# AI-EYE.net
KiCad netlist of a schematic drawn in Altium Designer
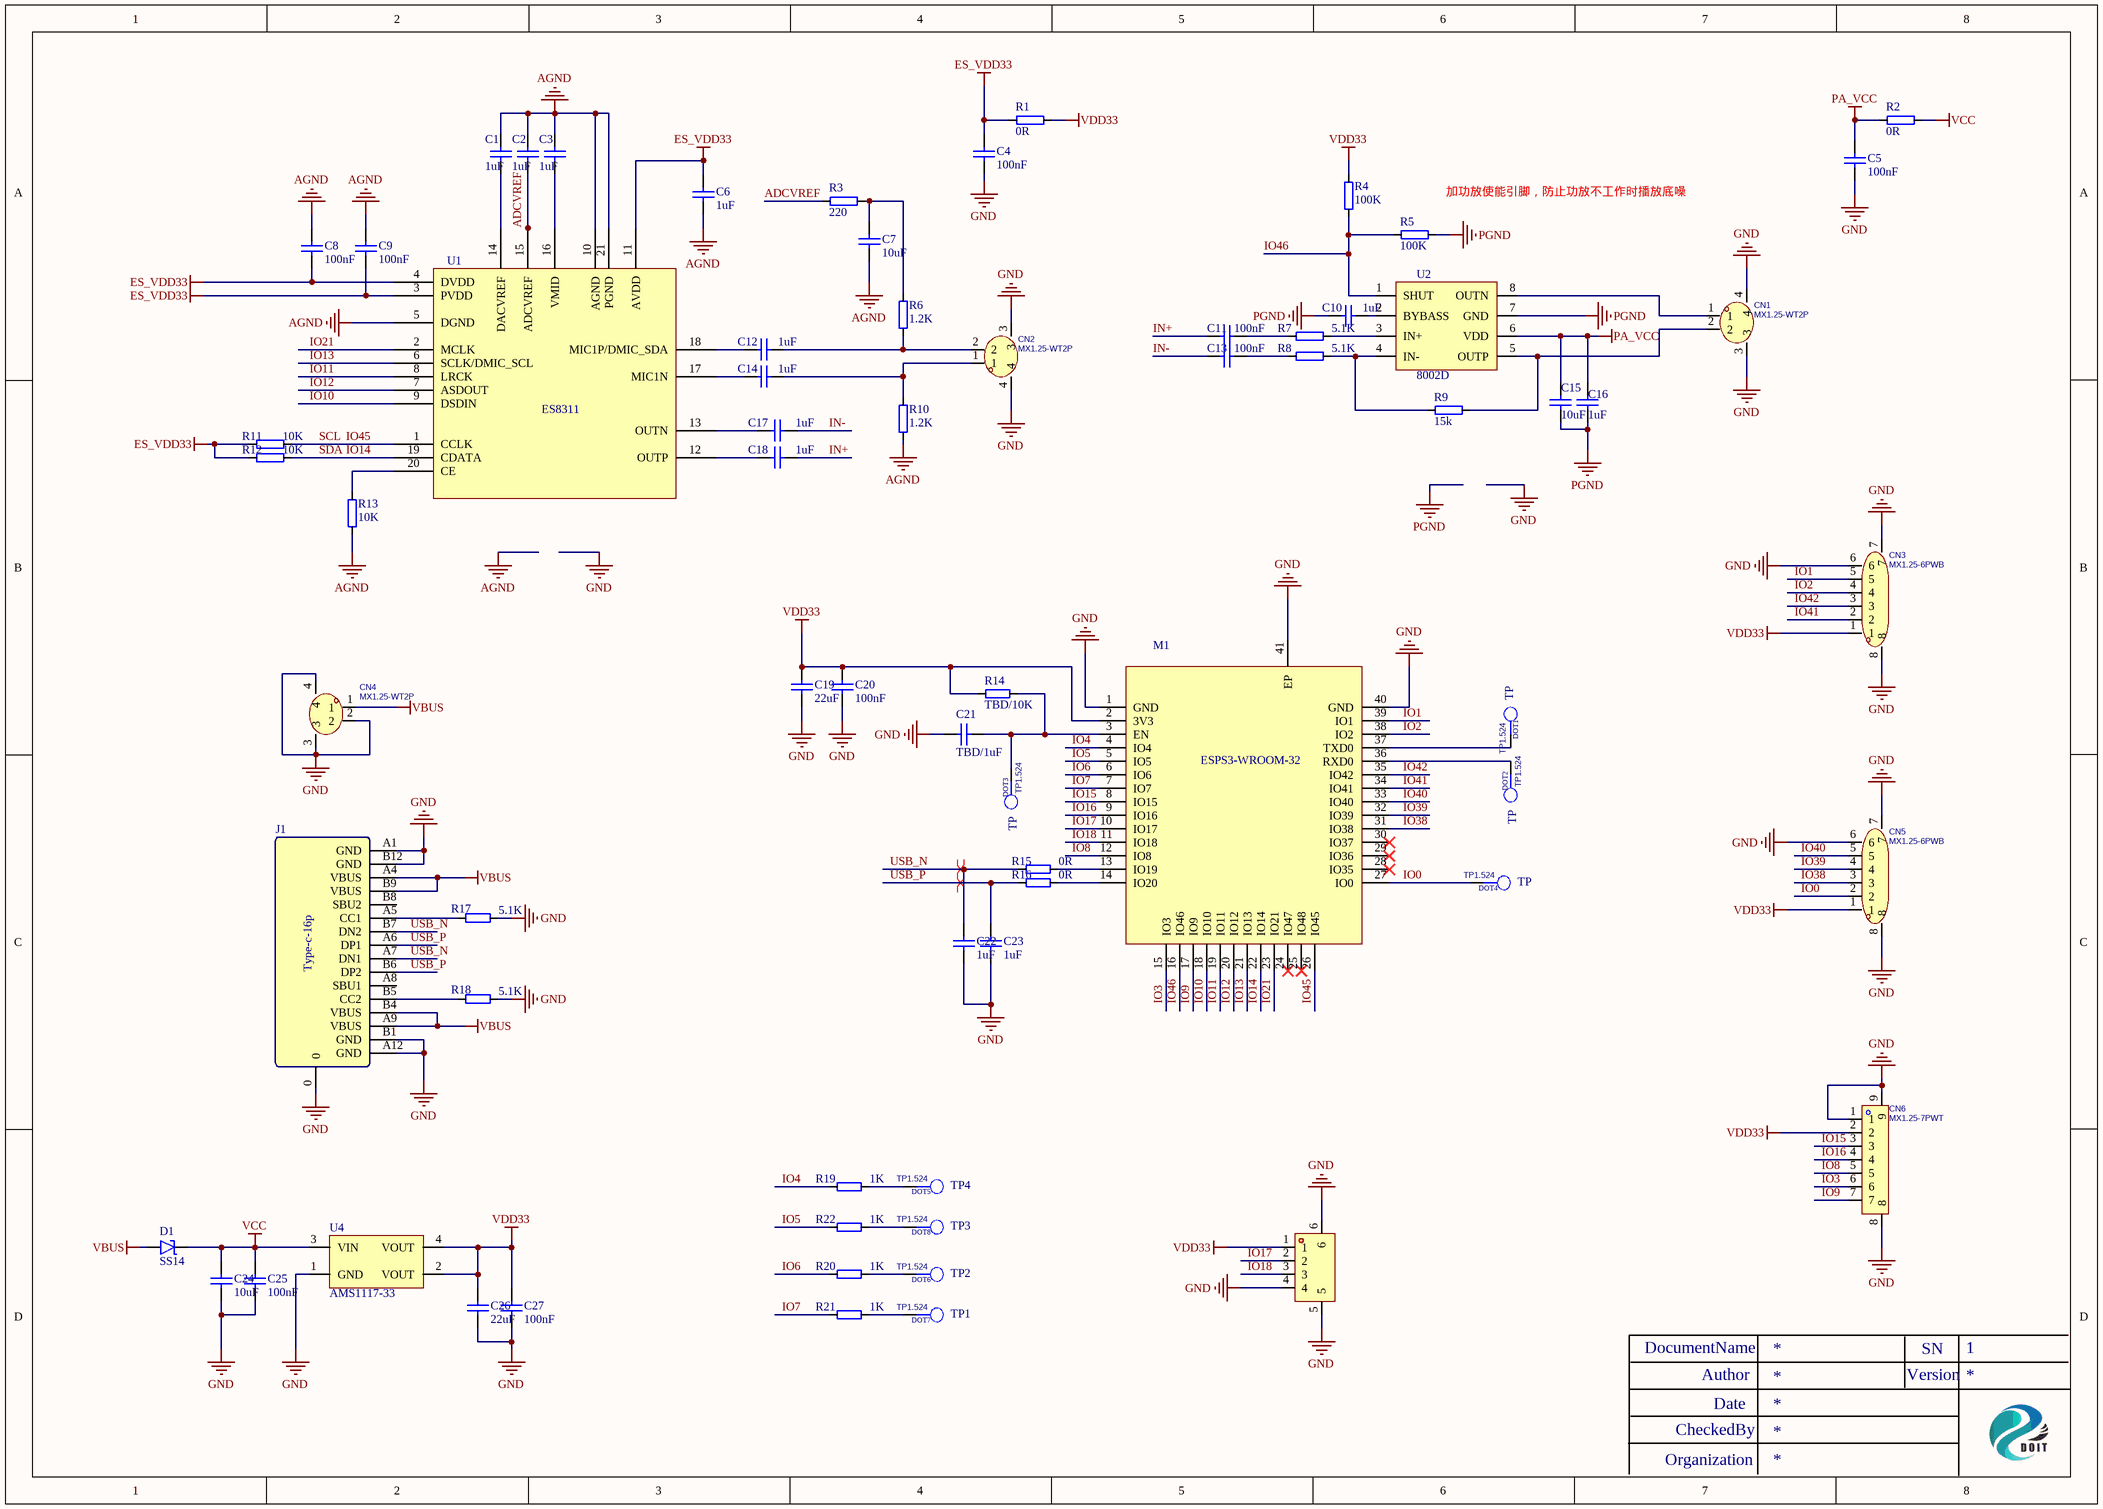
[diagram p0: AI-EYE.SchDoc]

(export (version "E")
  (design (tool "Eeschema 10.0.6"))
  (components
    (comp (ref "C1") (value "1uF") (footprint "0402C") (libsource (lib "accessory") (part "CAP-SMD")))
    (comp (ref "C2") (value "1uF") (footprint "0402C") (libsource (lib "accessory") (part "CAP-SMD")))
    (comp (ref "C3") (value "1uF") (footprint "0402C") (libsource (lib "accessory") (part "CAP-SMD")))
    (comp (ref "C4") (value "100nF") (footprint "0402C") (libsource (lib "accessory") (part "CAP-SMD")))
    (comp (ref "C5") (value "100nF") (footprint "0402C") (libsource (lib "accessory") (part "CAP-SMD")))
    (comp (ref "C6") (value "1uF") (footprint "0402C") (libsource (lib "accessory") (part "CAP-SMD")))
    (comp (ref "C7") (value "10uF") (footprint "0402C") (libsource (lib "accessory") (part "CAP-SMD")))
    (comp (ref "C8") (value "100nF") (footprint "0402C") (libsource (lib "accessory") (part "CAP-SMD")))
    (comp (ref "C9") (value "100nF") (footprint "0402C") (libsource (lib "accessory") (part "CAP-SMD")))
    (comp (ref "C10") (value "1uF") (footprint "0402C") (libsource (lib "accessory") (part "CAP-SMD")))
    (comp (ref "C11") (value "100nF") (footprint "0402C") (libsource (lib "accessory") (part "CAP-SMD")))
    (comp (ref "C12") (value "1uF") (footprint "0402C") (libsource (lib "accessory") (part "CAP-SMD")))
    (comp (ref "C13") (value "100nF") (footprint "0402C") (libsource (lib "accessory") (part "CAP-SMD")))
    (comp (ref "C14") (value "1uF") (footprint "0402C") (libsource (lib "accessory") (part "CAP-SMD")))
    (comp (ref "C15") (value "10uF") (footprint "0402C") (libsource (lib "accessory") (part "CAP-SMD")))
    (comp (ref "C16") (value "1uF") (footprint "0402C") (libsource (lib "accessory") (part "CAP-SMD")))
    (comp (ref "C17") (value "1uF") (footprint "0402C") (libsource (lib "accessory") (part "CAP-SMD")))
    (comp (ref "C18") (value "1uF") (footprint "0402C") (libsource (lib "accessory") (part "CAP-SMD")))
    (comp (ref "C19") (value "22uF") (footprint "0603C") (libsource (lib "accessory") (part "CAP-SMD")))
    (comp (ref "C20") (value "100nF") (footprint "0603C") (libsource (lib "accessory") (part "CAP-SMD")))
    (comp (ref "C21") (value "TBD/1uF") (footprint "0402C") (libsource (lib "accessory") (part "CAP-SMD")))
    (comp (ref "C22") (value "1uF") (footprint "0402C") (libsource (lib "accessory") (part "CAP-SMD")))
    (comp (ref "C23") (value "1uF") (footprint "0402C") (libsource (lib "accessory") (part "CAP-SMD")))
    (comp (ref "C24") (value "10uF") (footprint "0603C") (libsource (lib "accessory") (part "CAP-SMD")))
    (comp (ref "C25") (value "100nF") (footprint "0603C") (libsource (lib "accessory") (part "CAP-SMD")))
    (comp (ref "C26") (value "22uF") (footprint "0603C") (libsource (lib "accessory") (part "CAP-SMD")))
    (comp (ref "C27") (value "100nF") (footprint "0603C") (libsource (lib "accessory") (part "CAP-SMD")))
    (comp (ref "CN1")
      (value "MX1.25-WT2P")
      (footprint "CONN-SMD_2P-P1.25-WT2P")
      (fields (field (name "MANUFACTURER") "Megastar(兆星)"))
      (libsource (lib "connector") (part "CONN-MX1.25-2P"))
    )
    (comp (ref "CN2")
      (value "MX1.25-WT2P")
      (footprint "CONN-SMD_2P-P1.25-WT2P")
      (fields (field (name "MANUFACTURER") "Megastar(兆星)"))
      (libsource (lib "connector") (part "CONN-MX1.25-2P"))
    )
    (comp (ref "CN3")
      (value "MX1.25-6PWB")
      (footprint "CONN-SMD_6P-P1.25_XUNPU_WAFER-MX1.25-6PWB")
      (fields
        (field (name "MANUFACTURER") "XUNPU(讯普)")
        (field (name "MANUFACTURER PART") "WAFER-MX1.25-6PWB")
      )
      (libsource (lib "connector") (part "CONN-MX1.25-6PWB"))
    )
    (comp (ref "CN4")
      (value "MX1.25-WT2P")
      (footprint "CONN-SMD_2P-P1.25-WT2P")
      (fields (field (name "MANUFACTURER") "Megastar(兆星)"))
      (libsource (lib "connector") (part "CONN-MX1.25-2P"))
    )
    (comp (ref "CN5")
      (value "MX1.25-6PWB")
      (footprint "CONN-SMD_6P-P1.25_XUNPU_WAFER-MX1.25-6PWB")
      (fields
        (field (name "MANUFACTURER") "XUNPU(讯普)")
        (field (name "MANUFACTURER PART") "WAFER-MX1.25-6PWB")
      )
      (libsource (lib "connector") (part "CONN-MX1.25-6PWB"))
    )
    (comp (ref "CN6")
      (value "MX1.25-7PWT")
      (footprint "CONN-SMD_7P-P1.25_MX1.25-7PWT")
      (fields (field (name "MANUFACTURER") "Bossie(博锡)") (field (name "MANUFACTURER PART") "BX-MX1.25-7PWT"))
      (libsource (lib "connector") (part "CONN-MX1.25-7PWT"))
    )
    (comp (ref "D1")
      (value "SS14")
      (footprint "SOD123")
      (description "Schottky diode")
      (libsource (lib "accessory") (part "D"))
    )
    (comp (ref "DOT1")
      (value "TP")
      (footprint "TP-1.524")
      (fields (field (name "PCB FOOTPRINT") "TP1.524"))
      (libsource (lib "accessory") (part "TP"))
    )
    (comp (ref "DOT2")
      (value "TP")
      (footprint "TP-1.524")
      (fields (field (name "PCB FOOTPRINT") "TP1.524"))
      (libsource (lib "accessory") (part "TP"))
    )
    (comp (ref "DOT3")
      (value "TP")
      (footprint "TP-1.524")
      (fields (field (name "PCB FOOTPRINT") "TP1.524"))
      (libsource (lib "accessory") (part "TP"))
    )
    (comp (ref "DOT4")
      (value "TP")
      (footprint "TP-1.524")
      (fields (field (name "PCB FOOTPRINT") "TP1.524"))
      (libsource (lib "accessory") (part "TP"))
    )
    (comp (ref "DOT5")
      (value "TP4")
      (footprint "TP-5")
      (fields (field (name "PCB FOOTPRINT") "TP1.524"))
      (libsource (lib "accessory") (part "TP"))
    )
    (comp (ref "DOT6")
      (value "TP2")
      (footprint "TP-5")
      (fields (field (name "PCB FOOTPRINT") "TP1.524"))
      (libsource (lib "accessory") (part "TP"))
    )
    (comp (ref "DOT7")
      (value "TP1")
      (footprint "TP-5")
      (fields (field (name "PCB FOOTPRINT") "TP1.524"))
      (libsource (lib "accessory") (part "TP"))
    )
    (comp (ref "DOT8")
      (value "TP3")
      (footprint "TP-5")
      (fields (field (name "PCB FOOTPRINT") "TP1.524"))
      (libsource (lib "accessory") (part "TP"))
    )
    (comp (ref "J1")
      (value "Type-c-16p")
      (footprint "USB-TYPE-C")
      (libsource (lib "connector") (part "USB-TYPE-C"))
    )
    (comp (ref "M1")
      (value "ESPS3-WROOM-32")
      (footprint "ESPS3-WROOM-32")
      (libsource (lib "DOIT-MZ") (part "ESPS3-WROOM-32"))
    )
    (comp (ref "R1")
      (value "0R")
      (footprint "0402R")
      (description "Resistor")
      (libsource (lib "") (part "Res_1"))
    )
    (comp (ref "R2")
      (value "0R")
      (footprint "0402R")
      (description "Resistor")
      (libsource (lib "") (part "Res_1"))
    )
    (comp (ref "R3")
      (value "220")
      (footprint "0402R")
      (description "Resistor")
      (libsource (lib "") (part "Res_1"))
    )
    (comp (ref "R4")
      (value "100K")
      (footprint "0402R")
      (description "Resistor")
      (libsource (lib "") (part "Res_1"))
    )
    (comp (ref "R5")
      (value "100K")
      (footprint "0402R")
      (description "Resistor")
      (libsource (lib "") (part "Res_1"))
    )
    (comp (ref "R6")
      (value "1.2K")
      (footprint "0402R")
      (description "Resistor")
      (libsource (lib "") (part "Res_1"))
    )
    (comp (ref "R7")
      (value "5.1K")
      (footprint "0402R")
      (description "Resistor")
      (libsource (lib "") (part "Res_1"))
    )
    (comp (ref "R8")
      (value "5.1K")
      (footprint "0402R")
      (description "Resistor")
      (libsource (lib "") (part "Res_1"))
    )
    (comp (ref "R9")
      (value "15k")
      (footprint "0402R")
      (description "Resistor")
      (libsource (lib "") (part "Res_1"))
    )
    (comp (ref "R10")
      (value "1.2K")
      (footprint "0402R")
      (description "Resistor")
      (libsource (lib "") (part "Res_1"))
    )
    (comp (ref "R11")
      (value "10K")
      (footprint "0402R")
      (description "Resistor")
      (libsource (lib "") (part "Res_1"))
    )
    (comp (ref "R12")
      (value "10K")
      (footprint "0402R")
      (description "Resistor")
      (libsource (lib "") (part "Res_1"))
    )
    (comp (ref "R13")
      (value "10K")
      (footprint "0402R")
      (description "Resistor")
      (libsource (lib "") (part "Res_1"))
    )
    (comp (ref "R14")
      (value "TBD/10K")
      (footprint "0603R")
      (description "Resistor")
      (libsource (lib "accessory") (part "Res"))
    )
    (comp (ref "R15")
      (value "0R")
      (footprint "0402R")
      (description "Resistor")
      (libsource (lib "accessory") (part "Res"))
    )
    (comp (ref "R16")
      (value "0R")
      (footprint "0402R")
      (description "Resistor")
      (libsource (lib "accessory") (part "Res"))
    )
    (comp (ref "R17")
      (value "5.1K")
      (footprint "0402R")
      (description "Resistor")
      (libsource (lib "accessory") (part "Res"))
    )
    (comp (ref "R18")
      (value "5.1K")
      (footprint "0402R")
      (description "Resistor")
      (libsource (lib "accessory") (part "Res"))
    )
    (comp (ref "R19")
      (value "1K")
      (footprint "0402R")
      (description "Resistor")
      (libsource (lib "accessory") (part "Res"))
    )
    (comp (ref "R20")
      (value "1K")
      (footprint "0402R")
      (description "Resistor")
      (libsource (lib "accessory") (part "Res"))
    )
    (comp (ref "R21")
      (value "1K")
      (footprint "0402R")
      (description "Resistor")
      (libsource (lib "accessory") (part "Res"))
    )
    (comp (ref "R22")
      (value "1K")
      (footprint "0402R")
      (description "Resistor")
      (libsource (lib "accessory") (part "Res"))
    )
    (comp (ref "U1") (value "ES8311") (footprint "QFN-20-3X3") (libsource (lib "chip") (part "ES8311")))
    (comp (ref "U2") (value "8002D") (footprint "SOP8-1.27*5.4") (libsource (lib "chip") (part "8002D")))
    (comp (ref "U4") (value "AMS1117-33") (footprint "SOT-223") (libsource (lib "chip") (part "AMS1117-33")))
    (comp (ref "U5")
      (value "ZX-MX1.25-4PWT")
      (footprint "CONN-SMD_4P-P1.25-MX1.25-4P-WT")
      (fields (field (name "MANUFACTURER") "Megastar(兆星)"))
      (libsource (lib "connector") (part "CONN-MX1.25-4PWT"))
    )
  )
  (nets
    (net (code "1") (name "/ADCVREF") (class "Default")
      (node (ref "C2") (pin "1") (pinfunction "1_1") (pintype "passive"))
      (node (ref "R3") (pin "2") (pintype "passive"))
      (node (ref "U1") (pin "15") (pinfunction "ADCVREF_15") (pintype "passive"))
    )
    (net (code "2") (name "/IN+") (class "Default")
      (node (ref "C11") (pin "2") (pinfunction "2_2") (pintype "passive"))
      (node (ref "C18") (pin "1") (pinfunction "1_1") (pintype "passive"))
    )
    (net (code "3") (name "/IN-") (class "Default")
      (node (ref "C13") (pin "2") (pinfunction "2_2") (pintype "passive"))
      (node (ref "C17") (pin "1") (pinfunction "1_1") (pintype "passive"))
    )
    (net (code "4") (name "/IO0") (class "Default")
      (node (ref "CN5") (pin "2") (pinfunction "2_2") (pintype "passive"))
      (node (ref "DOT4") (pin "1") (pinfunction "1_1") (pintype "passive"))
      (node (ref "M1") (pin "27") (pinfunction "IO0_27") (pintype "passive"))
    )
    (net (code "5") (name "/IO1") (class "Default")
      (node (ref "CN3") (pin "5") (pinfunction "5_5") (pintype "passive"))
      (node (ref "M1") (pin "39") (pinfunction "IO1_39") (pintype "passive"))
    )
    (net (code "6") (name "/IO2") (class "Default")
      (node (ref "CN3") (pin "4") (pinfunction "4_4") (pintype "passive"))
      (node (ref "M1") (pin "38") (pinfunction "IO2_38") (pintype "passive"))
    )
    (net (code "7") (name "/IO3") (class "Default")
      (node (ref "CN6") (pin "6") (pinfunction "6_6") (pintype "passive"))
      (node (ref "M1") (pin "15") (pinfunction "IO3_15") (pintype "passive"))
    )
    (net (code "8") (name "/IO4") (class "Default")
      (node (ref "M1") (pin "4") (pinfunction "IO4_4") (pintype "passive"))
      (node (ref "R19") (pin "2") (pintype "passive"))
    )
    (net (code "9") (name "/IO5") (class "Default")
      (node (ref "M1") (pin "5") (pinfunction "IO5_5") (pintype "passive"))
      (node (ref "R22") (pin "2") (pintype "passive"))
    )
    (net (code "10") (name "/IO6") (class "Default")
      (node (ref "M1") (pin "6") (pinfunction "IO6_6") (pintype "passive"))
      (node (ref "R20") (pin "2") (pintype "passive"))
    )
    (net (code "11") (name "/IO7") (class "Default")
      (node (ref "M1") (pin "7") (pinfunction "IO7_7") (pintype "passive"))
      (node (ref "R21") (pin "2") (pintype "passive"))
    )
    (net (code "12") (name "/IO8") (class "Default")
      (node (ref "CN6") (pin "5") (pinfunction "5_5") (pintype "passive"))
      (node (ref "M1") (pin "12") (pinfunction "IO8_12") (pintype "passive"))
    )
    (net (code "13") (name "/IO9") (class "Default")
      (node (ref "CN6") (pin "7") (pinfunction "7_7") (pintype "passive"))
      (node (ref "M1") (pin "17") (pinfunction "IO9_17") (pintype "passive"))
    )
    (net (code "14") (name "/IO10") (class "Default")
      (node (ref "M1") (pin "18") (pinfunction "IO10_18") (pintype "passive"))
      (node (ref "U1") (pin "9") (pinfunction "DSDIN_9") (pintype "passive"))
    )
    (net (code "15") (name "/IO11") (class "Default")
      (node (ref "M1") (pin "19") (pinfunction "IO11_19") (pintype "passive"))
      (node (ref "U1") (pin "8") (pinfunction "LRCK_8") (pintype "passive"))
    )
    (net (code "16") (name "/IO12") (class "Default")
      (node (ref "M1") (pin "20") (pinfunction "IO12_20") (pintype "passive"))
      (node (ref "U1") (pin "7") (pinfunction "ASDOUT_7") (pintype "passive"))
    )
    (net (code "17") (name "/IO13") (class "Default")
      (node (ref "M1") (pin "21") (pinfunction "IO13_21") (pintype "passive"))
      (node (ref "U1") (pin "6") (pinfunction "SCLK/DMIC_SCL_6") (pintype "passive"))
    )
    (net (code "18") (name "/IO14") (class "Default")
      (node (ref "M1") (pin "22") (pinfunction "IO14_22") (pintype "passive"))
      (node (ref "R12") (pin "2") (pintype "passive"))
      (node (ref "U1") (pin "19") (pinfunction "CDATA_19") (pintype "passive"))
    )
    (net (code "19") (name "/IO15") (class "Default")
      (node (ref "CN6") (pin "3") (pinfunction "3_3") (pintype "passive"))
      (node (ref "M1") (pin "8") (pinfunction "IO15_8") (pintype "passive"))
    )
    (net (code "20") (name "/IO16") (class "Default")
      (node (ref "CN6") (pin "4") (pinfunction "4_4") (pintype "passive"))
      (node (ref "M1") (pin "9") (pinfunction "IO16_9") (pintype "passive"))
    )
    (net (code "21") (name "/IO17") (class "Default")
      (node (ref "M1") (pin "10") (pinfunction "IO17_10") (pintype "passive"))
      (node (ref "U5") (pin "2") (pinfunction "2_2") (pintype "passive"))
    )
    (net (code "22") (name "/IO18") (class "Default")
      (node (ref "M1") (pin "11") (pinfunction "IO18_11") (pintype "passive"))
      (node (ref "U5") (pin "3") (pinfunction "3_3") (pintype "passive"))
    )
    (net (code "23") (name "/IO21") (class "Default")
      (node (ref "M1") (pin "23") (pinfunction "IO21_23") (pintype "passive"))
      (node (ref "U1") (pin "2") (pinfunction "MCLK_2") (pintype "passive"))
    )
    (net (code "24") (name "/IO38") (class "Default")
      (node (ref "CN5") (pin "3") (pinfunction "3_3") (pintype "passive"))
      (node (ref "M1") (pin "31") (pinfunction "IO38_31") (pintype "passive"))
    )
    (net (code "25") (name "/IO39") (class "Default")
      (node (ref "CN5") (pin "4") (pinfunction "4_4") (pintype "passive"))
      (node (ref "M1") (pin "32") (pinfunction "IO39_32") (pintype "passive"))
    )
    (net (code "26") (name "/IO40") (class "Default")
      (node (ref "CN5") (pin "5") (pinfunction "5_5") (pintype "passive"))
      (node (ref "M1") (pin "33") (pinfunction "IO40_33") (pintype "passive"))
    )
    (net (code "27") (name "/IO41") (class "Default")
      (node (ref "CN3") (pin "2") (pinfunction "2_2") (pintype "passive"))
      (node (ref "M1") (pin "34") (pinfunction "IO41_34") (pintype "passive"))
    )
    (net (code "28") (name "/IO42") (class "Default")
      (node (ref "CN3") (pin "3") (pinfunction "3_3") (pintype "passive"))
      (node (ref "M1") (pin "35") (pinfunction "IO42_35") (pintype "passive"))
    )
    (net (code "29") (name "/IO45") (class "Default")
      (node (ref "M1") (pin "26") (pinfunction "IO45_26") (pintype "passive"))
      (node (ref "R11") (pin "2") (pintype "passive"))
      (node (ref "U1") (pin "1") (pinfunction "CCLK_1") (pintype "passive"))
    )
    (net (code "30") (name "/IO46") (class "Default")
      (node (ref "M1") (pin "16") (pinfunction "IO46_16") (pintype "passive"))
      (node (ref "R4") (pin "2") (pintype "passive"))
      (node (ref "R5") (pin "1") (pintype "passive"))
      (node (ref "U2") (pin "1") (pinfunction "SHUT_1") (pintype "passive"))
    )
    (net (code "31") (name "/USB_N") (class "Default")
      (node (ref "C22") (pin "1") (pinfunction "1_1") (pintype "passive"))
      (node (ref "J1") (pin "A7") (pinfunction "DN1_A7") (pintype "passive"))
      (node (ref "J1") (pin "B7") (pinfunction "DN2_B7") (pintype "passive"))
      (node (ref "R15") (pin "2") (pintype "passive"))
    )
    (net (code "32") (name "/USB_P") (class "Default")
      (node (ref "C23") (pin "1") (pinfunction "1_1") (pintype "passive"))
      (node (ref "J1") (pin "A6") (pinfunction "DP1_A6") (pintype "passive"))
      (node (ref "J1") (pin "B6") (pinfunction "DP2_B6") (pintype "passive"))
      (node (ref "R16") (pin "2") (pintype "passive"))
    )
    (net (code "33") (name "AGND") (class "Default")
      (node (ref "C1") (pin "2") (pinfunction "2_2") (pintype "passive"))
      (node (ref "C2") (pin "2") (pinfunction "2_2") (pintype "passive"))
      (node (ref "C3") (pin "2") (pinfunction "2_2") (pintype "passive"))
      (node (ref "C6") (pin "1") (pinfunction "1_1") (pintype "passive"))
      (node (ref "C7") (pin "2") (pinfunction "2_2") (pintype "passive"))
      (node (ref "C8") (pin "2") (pinfunction "2_2") (pintype "passive"))
      (node (ref "C9") (pin "2") (pinfunction "2_2") (pintype "passive"))
      (node (ref "R10") (pin "2") (pintype "passive"))
      (node (ref "R13") (pin "2") (pintype "passive"))
      (node (ref "U1") (pin "10") (pinfunction "AGND_10") (pintype "passive"))
      (node (ref "U1") (pin "21") (pinfunction "PGND_21") (pintype "passive"))
      (node (ref "U1") (pin "5") (pinfunction "DGND_5") (pintype "passive"))
    )
    (net (code "34") (name "ES_VDD33") (class "Default")
      (node (ref "C4") (pin "2") (pinfunction "2_2") (pintype "passive"))
      (node (ref "C6") (pin "2") (pinfunction "2_2") (pintype "passive"))
      (node (ref "C8") (pin "1") (pinfunction "1_1") (pintype "passive"))
      (node (ref "C9") (pin "1") (pinfunction "1_1") (pintype "passive"))
      (node (ref "R1") (pin "2") (pintype "passive"))
      (node (ref "R11") (pin "1") (pintype "passive"))
      (node (ref "R12") (pin "1") (pintype "passive"))
      (node (ref "U1") (pin "11") (pinfunction "AVDD_11") (pintype "passive"))
      (node (ref "U1") (pin "3") (pinfunction "PVDD_3") (pintype "passive"))
      (node (ref "U1") (pin "4") (pinfunction "DVDD_4") (pintype "passive"))
    )
    (net (code "35") (name "GND") (class "Default")
      (node (ref "C19") (pin "2") (pinfunction "2_2") (pintype "passive"))
      (node (ref "C20") (pin "2") (pinfunction "2_2") (pintype "passive"))
      (node (ref "C21") (pin "1") (pinfunction "1_1") (pintype "passive"))
      (node (ref "C22") (pin "2") (pinfunction "2_2") (pintype "passive"))
      (node (ref "C23") (pin "2") (pinfunction "2_2") (pintype "passive"))
      (node (ref "C24") (pin "2") (pinfunction "2_2") (pintype "passive"))
      (node (ref "C25") (pin "2") (pinfunction "2_2") (pintype "passive"))
      (node (ref "C26") (pin "2") (pinfunction "2_2") (pintype "passive"))
      (node (ref "C27") (pin "2") (pinfunction "2_2") (pintype "passive"))
      (node (ref "C4") (pin "1") (pinfunction "1_1") (pintype "passive"))
      (node (ref "C5") (pin "1") (pinfunction "1_1") (pintype "passive"))
      (node (ref "CN1") (pin "3") (pinfunction "3_3") (pintype "passive"))
      (node (ref "CN1") (pin "4") (pinfunction "4_4") (pintype "passive"))
      (node (ref "CN2") (pin "3") (pinfunction "3_3") (pintype "passive"))
      (node (ref "CN2") (pin "4") (pinfunction "4_4") (pintype "passive"))
      (node (ref "CN3") (pin "6") (pinfunction "6_6") (pintype "passive"))
      (node (ref "CN3") (pin "7") (pinfunction "7_7") (pintype "passive"))
      (node (ref "CN3") (pin "8") (pinfunction "8_8") (pintype "passive"))
      (node (ref "CN4") (pin "2") (pinfunction "2_2") (pintype "passive"))
      (node (ref "CN4") (pin "3") (pinfunction "3_3") (pintype "passive"))
      (node (ref "CN4") (pin "4") (pinfunction "4_4") (pintype "passive"))
      (node (ref "CN5") (pin "6") (pinfunction "6_6") (pintype "passive"))
      (node (ref "CN5") (pin "7") (pinfunction "7_7") (pintype "passive"))
      (node (ref "CN5") (pin "8") (pinfunction "8_8") (pintype "passive"))
      (node (ref "CN6") (pin "1") (pinfunction "1_1") (pintype "passive"))
      (node (ref "CN6") (pin "8") (pinfunction "8_8") (pintype "passive"))
      (node (ref "CN6") (pin "9") (pinfunction "9_9") (pintype "passive"))
      (node (ref "J1") (pin "0") (pinfunction "0_0") (pintype "passive"))
      (node (ref "J1") (pin "A1") (pinfunction "GND_A1") (pintype "passive"))
      (node (ref "J1") (pin "A12") (pinfunction "GND_A12") (pintype "passive"))
      (node (ref "J1") (pin "B1") (pinfunction "GND_B1") (pintype "passive"))
      (node (ref "J1") (pin "B12") (pinfunction "GND_B12") (pintype "passive"))
      (node (ref "M1") (pin "1") (pinfunction "GND_1") (pintype "passive"))
      (node (ref "M1") (pin "40") (pinfunction "GND_40") (pintype "passive"))
      (node (ref "M1") (pin "41") (pinfunction "EP_41") (pintype "passive"))
      (node (ref "R17") (pin "1") (pintype "passive"))
      (node (ref "R18") (pin "1") (pintype "passive"))
      (node (ref "U4") (pin "1") (pinfunction "GND_1") (pintype "passive"))
      (node (ref "U5") (pin "4") (pinfunction "4_4") (pintype "passive"))
      (node (ref "U5") (pin "5") (pinfunction "5_5") (pintype "passive"))
      (node (ref "U5") (pin "6") (pinfunction "6_6") (pintype "passive"))
    )
    (net (code "36") (name "Net-(C7-Pad1)") (class "Default")
      (node (ref "C7") (pin "1") (pinfunction "1_1") (pintype "passive"))
      (node (ref "R3") (pin "1") (pintype "passive"))
      (node (ref "R6") (pin "2") (pintype "passive"))
    )
    (net (code "37") (name "Net-(C11-Pad1)") (class "Default")
      (node (ref "C11") (pin "1") (pinfunction "1_1") (pintype "passive"))
      (node (ref "R7") (pin "2") (pintype "passive"))
    )
    (net (code "38") (name "Net-(C12-Pad1)") (class "Default")
      (node (ref "C12") (pin "1") (pinfunction "1_1") (pintype "passive"))
      (node (ref "CN2") (pin "2") (pinfunction "2_2") (pintype "passive"))
      (node (ref "R6") (pin "1") (pintype "passive"))
    )
    (net (code "39") (name "Net-(C13-Pad1)") (class "Default")
      (node (ref "C13") (pin "1") (pinfunction "1_1") (pintype "passive"))
      (node (ref "R8") (pin "2") (pintype "passive"))
    )
    (net (code "40") (name "Net-(C14-Pad1)") (class "Default")
      (node (ref "C14") (pin "1") (pinfunction "1_1") (pintype "passive"))
      (node (ref "CN2") (pin "1") (pinfunction "1_1") (pintype "passive"))
      (node (ref "R10") (pin "1") (pintype "passive"))
    )
    (net (code "41") (name "Net-(DOT5-Pad1)") (class "Default")
      (node (ref "DOT5") (pin "1") (pinfunction "1_1") (pintype "passive"))
      (node (ref "R19") (pin "1") (pintype "passive"))
    )
    (net (code "42") (name "Net-(DOT6-Pad1)") (class "Default")
      (node (ref "DOT6") (pin "1") (pinfunction "1_1") (pintype "passive"))
      (node (ref "R20") (pin "1") (pintype "passive"))
    )
    (net (code "43") (name "Net-(DOT7-Pad1)") (class "Default")
      (node (ref "DOT7") (pin "1") (pinfunction "1_1") (pintype "passive"))
      (node (ref "R21") (pin "1") (pintype "passive"))
    )
    (net (code "44") (name "Net-(DOT8-Pad1)") (class "Default")
      (node (ref "DOT8") (pin "1") (pinfunction "1_1") (pintype "passive"))
      (node (ref "R22") (pin "1") (pintype "passive"))
    )
    (net (code "45") (name "Net-(J1-CC1)") (class "Default")
      (node (ref "J1") (pin "A5") (pinfunction "CC1_A5") (pintype "passive"))
      (node (ref "R17") (pin "2") (pintype "passive"))
    )
    (net (code "46") (name "Net-(J1-CC2)") (class "Default")
      (node (ref "J1") (pin "B5") (pinfunction "CC2_B5") (pintype "passive"))
      (node (ref "R18") (pin "2") (pintype "passive"))
    )
    (net (code "47") (name "Net-(M1-EN)") (class "Default")
      (node (ref "C21") (pin "2") (pinfunction "2_2") (pintype "passive"))
      (node (ref "DOT3") (pin "1") (pinfunction "1_1") (pintype "passive"))
      (node (ref "M1") (pin "3") (pinfunction "EN_3") (pintype "passive"))
      (node (ref "R14") (pin "2") (pintype "passive"))
    )
    (net (code "48") (name "Net-(M1-IO19)") (class "Default")
      (node (ref "M1") (pin "13") (pinfunction "IO19_13") (pintype "passive"))
      (node (ref "R15") (pin "1") (pintype "passive"))
    )
    (net (code "49") (name "Net-(M1-IO20)") (class "Default")
      (node (ref "M1") (pin "14") (pinfunction "IO20_14") (pintype "passive"))
      (node (ref "R16") (pin "1") (pintype "passive"))
    )
    (net (code "50") (name "Net-(M1-RXD0)") (class "Default")
      (node (ref "DOT2") (pin "1") (pinfunction "1_1") (pintype "passive"))
      (node (ref "M1") (pin "36") (pinfunction "RXD0_36") (pintype "passive"))
    )
    (net (code "51") (name "Net-(M1-TXD0)") (class "Default")
      (node (ref "DOT1") (pin "1") (pinfunction "1_1") (pintype "passive"))
      (node (ref "M1") (pin "37") (pinfunction "TXD0_37") (pintype "passive"))
    )
    (net (code "52") (name "Net-(U1-CE)") (class "Default")
      (node (ref "R13") (pin "1") (pintype "passive"))
      (node (ref "U1") (pin "20") (pinfunction "CE_20") (pintype "passive"))
    )
    (net (code "53") (name "Net-(U1-DACVREF)") (class "Default")
      (node (ref "C1") (pin "1") (pinfunction "1_1") (pintype "passive"))
      (node (ref "U1") (pin "14") (pinfunction "DACVREF_14") (pintype "passive"))
    )
    (net (code "54") (name "Net-(U1-MIC1N)") (class "Default")
      (node (ref "C14") (pin "2") (pinfunction "2_2") (pintype "passive"))
      (node (ref "U1") (pin "17") (pinfunction "MIC1N_17") (pintype "passive"))
    )
    (net (code "55") (name "Net-(U1-MIC1P{slash}DMIC_SDA)") (class "Default")
      (node (ref "C12") (pin "2") (pinfunction "2_2") (pintype "passive"))
      (node (ref "U1") (pin "18") (pinfunction "MIC1P/DMIC_SDA_18") (pintype "passive"))
    )
    (net (code "56") (name "Net-(U1-OUTN)") (class "Default")
      (node (ref "C17") (pin "2") (pinfunction "2_2") (pintype "passive"))
      (node (ref "U1") (pin "13") (pinfunction "OUTN_13") (pintype "passive"))
    )
    (net (code "57") (name "Net-(U1-OUTP)") (class "Default")
      (node (ref "C18") (pin "2") (pinfunction "2_2") (pintype "passive"))
      (node (ref "U1") (pin "12") (pinfunction "OUTP_12") (pintype "passive"))
    )
    (net (code "58") (name "Net-(U1-VMID)") (class "Default")
      (node (ref "C3") (pin "1") (pinfunction "1_1") (pintype "passive"))
      (node (ref "U1") (pin "16") (pinfunction "VMID_16") (pintype "passive"))
    )
    (net (code "59") (name "Net-(U2-BYBASS)") (class "Default")
      (node (ref "C10") (pin "1") (pinfunction "1_1") (pintype "passive"))
      (node (ref "U2") (pin "2") (pinfunction "BYBASS_2") (pintype "passive"))
    )
    (net (code "60") (name "Net-(U2-IN+)") (class "Default")
      (node (ref "R7") (pin "1") (pintype "passive"))
      (node (ref "U2") (pin "3") (pinfunction "IN+_3") (pintype "passive"))
    )
    (net (code "61") (name "Net-(U2-IN-)") (class "Default")
      (node (ref "R8") (pin "1") (pintype "passive"))
      (node (ref "R9") (pin "1") (pintype "passive"))
      (node (ref "U2") (pin "4") (pinfunction "IN-_4") (pintype "passive"))
    )
    (net (code "62") (name "Net-(U2-OUTN)") (class "Default")
      (node (ref "CN1") (pin "1") (pinfunction "1_1") (pintype "passive"))
      (node (ref "U2") (pin "8") (pinfunction "OUTN_8") (pintype "passive"))
    )
    (net (code "63") (name "Net-(U2-OUTP)") (class "Default")
      (node (ref "CN1") (pin "2") (pinfunction "2_2") (pintype "passive"))
      (node (ref "R9") (pin "2") (pintype "passive"))
      (node (ref "U2") (pin "5") (pinfunction "OUTP_5") (pintype "passive"))
    )
    (net (code "64") (name "PA_VCC") (class "Default")
      (node (ref "C15") (pin "1") (pinfunction "1_1") (pintype "passive"))
      (node (ref "C16") (pin "1") (pinfunction "1_1") (pintype "passive"))
      (node (ref "C5") (pin "2") (pinfunction "2_2") (pintype "passive"))
      (node (ref "R2") (pin "2") (pintype "passive"))
      (node (ref "U2") (pin "6") (pinfunction "VDD_6") (pintype "passive"))
    )
    (net (code "65") (name "PGND") (class "Default")
      (node (ref "C10") (pin "2") (pinfunction "2_2") (pintype "passive"))
      (node (ref "C15") (pin "2") (pinfunction "2_2") (pintype "passive"))
      (node (ref "C16") (pin "2") (pinfunction "2_2") (pintype "passive"))
      (node (ref "R5") (pin "2") (pintype "passive"))
      (node (ref "U2") (pin "7") (pinfunction "GND_7") (pintype "passive"))
    )
    (net (code "66") (name "VBUS") (class "Default")
      (node (ref "CN4") (pin "1") (pinfunction "1_1") (pintype "passive"))
      (node (ref "D1") (pin "1") (pinfunction "1_1") (pintype "passive"))
      (node (ref "J1") (pin "A4") (pinfunction "VBUS_A4") (pintype "passive"))
      (node (ref "J1") (pin "A9") (pinfunction "VBUS_A9") (pintype "passive"))
      (node (ref "J1") (pin "B4") (pinfunction "VBUS_B4") (pintype "passive"))
      (node (ref "J1") (pin "B9") (pinfunction "VBUS_B9") (pintype "passive"))
    )
    (net (code "67") (name "VCC") (class "Default")
      (node (ref "C24") (pin "1") (pinfunction "1_1") (pintype "passive"))
      (node (ref "C25") (pin "1") (pinfunction "1_1") (pintype "passive"))
      (node (ref "D1") (pin "2") (pinfunction "2_2") (pintype "passive"))
      (node (ref "R2") (pin "1") (pintype "passive"))
      (node (ref "U4") (pin "3") (pinfunction "VIN_3") (pintype "passive"))
    )
    (net (code "68") (name "VDD33") (class "Default")
      (node (ref "C19") (pin "1") (pinfunction "1_1") (pintype "passive"))
      (node (ref "C20") (pin "1") (pinfunction "1_1") (pintype "passive"))
      (node (ref "C26") (pin "1") (pinfunction "1_1") (pintype "passive"))
      (node (ref "C27") (pin "1") (pinfunction "1_1") (pintype "passive"))
      (node (ref "CN3") (pin "1") (pinfunction "1_1") (pintype "passive"))
      (node (ref "CN5") (pin "1") (pinfunction "1_1") (pintype "passive"))
      (node (ref "CN6") (pin "2") (pinfunction "2_2") (pintype "passive"))
      (node (ref "M1") (pin "2") (pinfunction "3V3_2") (pintype "passive"))
      (node (ref "R1") (pin "1") (pintype "passive"))
      (node (ref "R14") (pin "1") (pintype "passive"))
      (node (ref "R4") (pin "1") (pintype "passive"))
      (node (ref "U4") (pin "2") (pinfunction "VOUT_2") (pintype "passive"))
      (node (ref "U4") (pin "4") (pinfunction "VOUT_4") (pintype "passive"))
      (node (ref "U5") (pin "1") (pinfunction "1_1") (pintype "passive"))
    )
    (net (code "69") (name "unconnected-(J1-SBU1-PadA8)") (class "Default")
      (node (ref "J1") (pin "A8") (pinfunction "SBU1_A8") (pintype "passive"))
    )
    (net (code "70") (name "unconnected-(J1-SBU2-PadB8)") (class "Default")
      (node (ref "J1") (pin "B8") (pinfunction "SBU2_B8") (pintype "passive"))
    )
    (net (code "71") (name "unconnected-(M1-IO35-Pad28)") (class "Default")
      (node (ref "M1") (pin "28") (pinfunction "IO35_28") (pintype "passive+no_connect"))
    )
    (net (code "72") (name "unconnected-(M1-IO36-Pad29)") (class "Default")
      (node (ref "M1") (pin "29") (pinfunction "IO36_29") (pintype "passive+no_connect"))
    )
    (net (code "73") (name "unconnected-(M1-IO37-Pad30)") (class "Default")
      (node (ref "M1") (pin "30") (pinfunction "IO37_30") (pintype "passive+no_connect"))
    )
    (net (code "74") (name "unconnected-(M1-IO47-Pad24)") (class "Default")
      (node (ref "M1") (pin "24") (pinfunction "IO47_24") (pintype "passive+no_connect"))
    )
    (net (code "75") (name "unconnected-(M1-IO48-Pad25)") (class "Default")
      (node (ref "M1") (pin "25") (pinfunction "IO48_25") (pintype "passive+no_connect"))
    )
  )
)
